# Sheme.net
KiCad netlist of a schematic drawn in Altium Designer
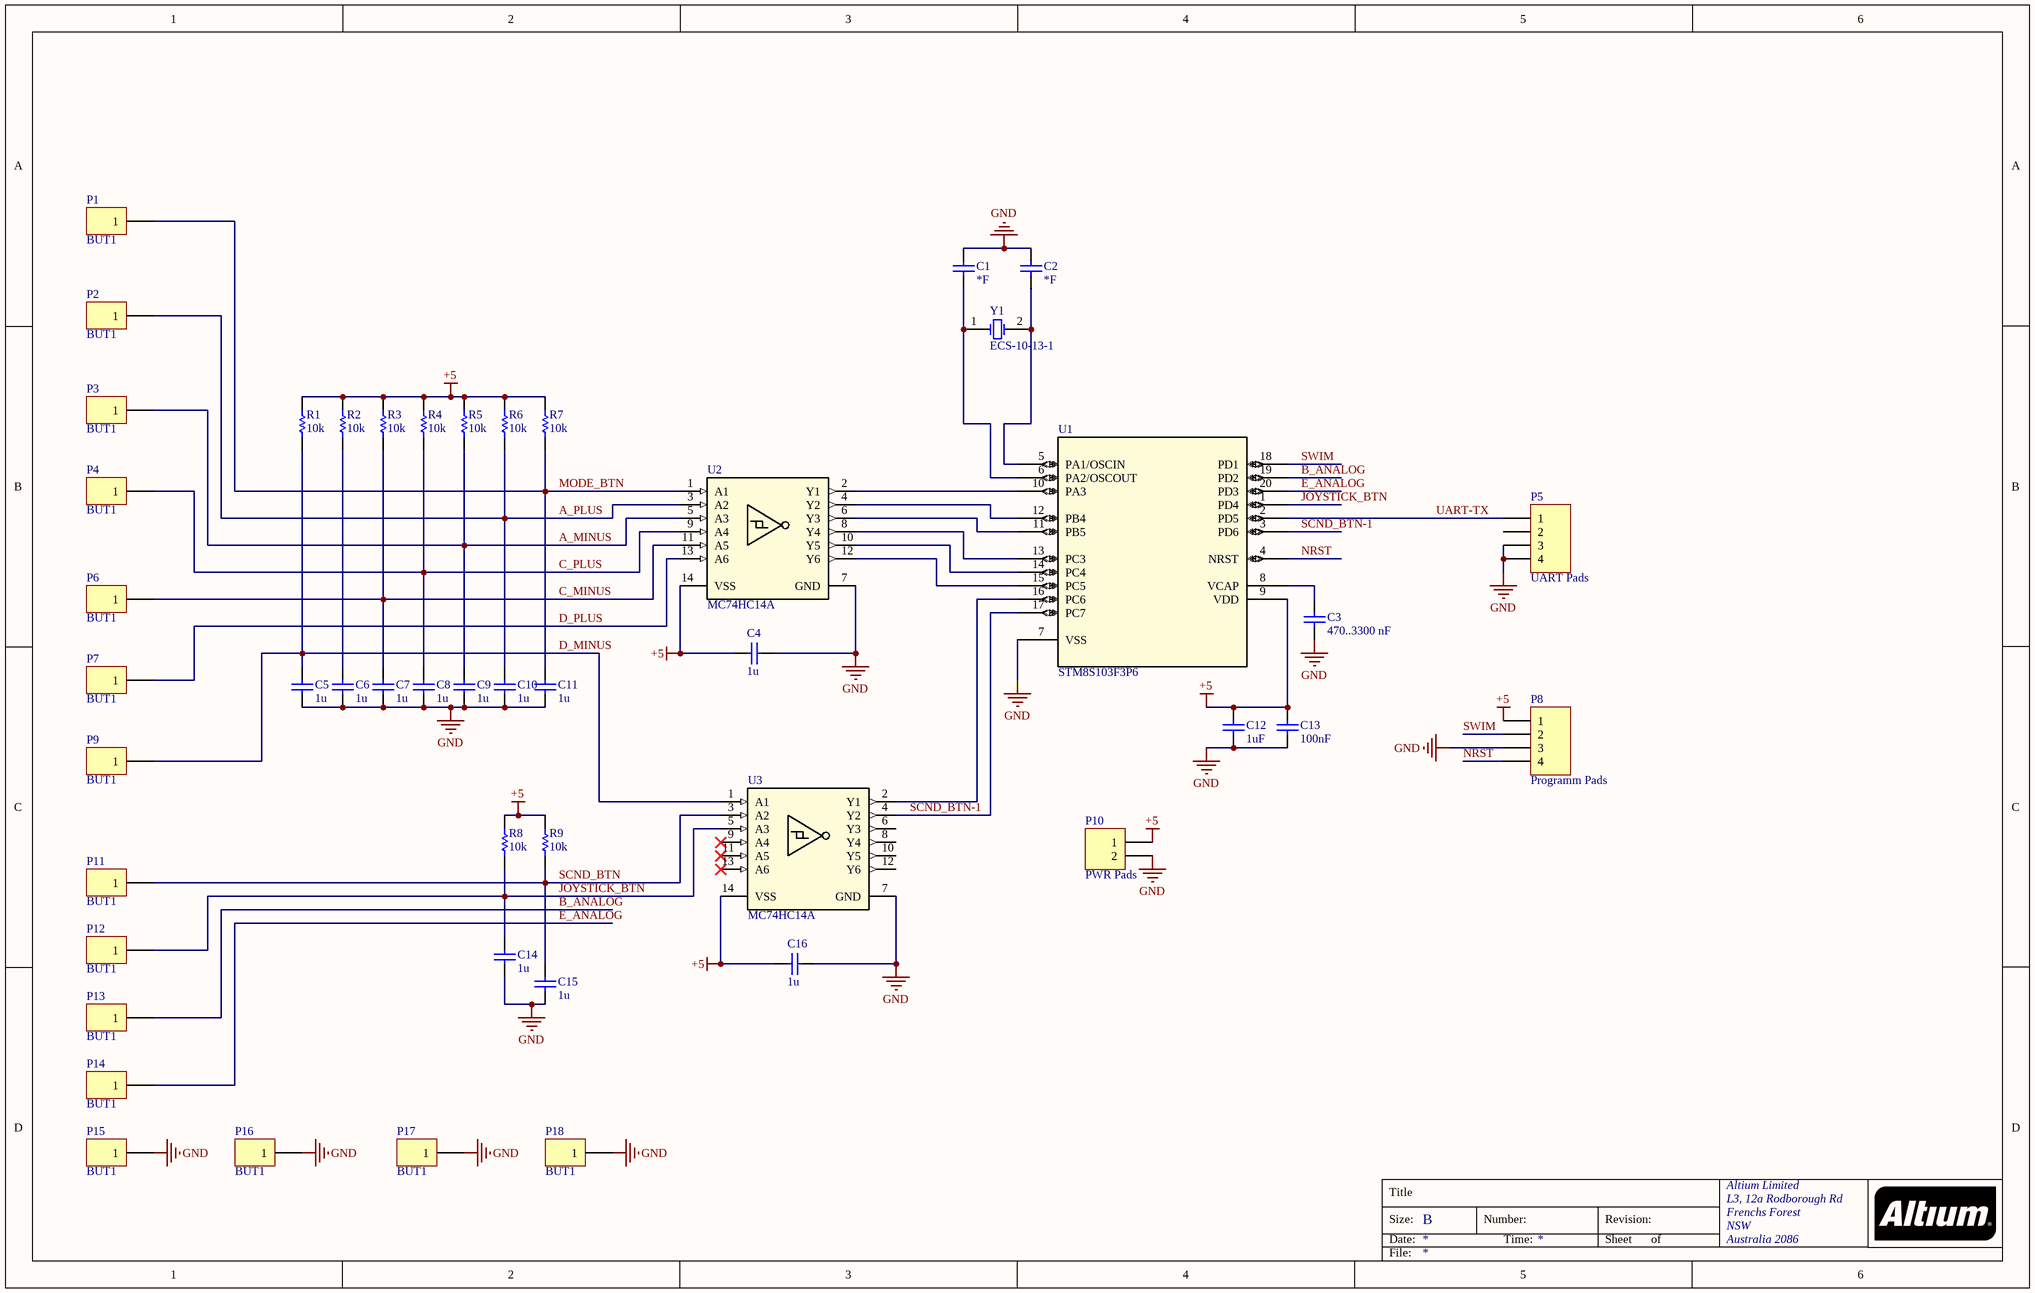
[diagram p0: Sheme.SchDoc]

(export (version "E")
  (design (tool "Eeschema 10.0.6"))
  (components
    (comp (ref "C1")
      (value "*F")
      (footprint "C0805")
      (description "Capacitor ceramic SMD")
      (fields (field (name "MANUFACTURER") "Murata") (field (name "Comment") "Cap"))
      (libsource (lib "DriverBoardForCNC") (part "Cap"))
    )
    (comp (ref "C2")
      (value "*F")
      (footprint "C0805")
      (description "Capacitor ceramic SMD")
      (fields (field (name "MANUFACTURER") "Murata") (field (name "Comment") "Cap"))
      (libsource (lib "DriverBoardForCNC") (part "Cap"))
    )
    (comp (ref "C3")
      (value "470..3300 nF")
      (footprint "C0805")
      (description "Capacitor ceramic SMD")
      (fields (field (name "MANUFACTURER") "Murata") (field (name "Comment") "Cap"))
      (libsource (lib "DriverBoardForCNC") (part "Cap"))
    )
    (comp (ref "C4")
      (value "1u")
      (footprint "C0805")
      (description "Capacitor ceramic SMD")
      (fields (field (name "MANUFACTURER") "Murata") (field (name "Comment") "Cap"))
      (libsource (lib "DriverBoardForCNC") (part "Cap"))
    )
    (comp (ref "C5")
      (value "1u")
      (footprint "C0805")
      (description "Capacitor ceramic SMD")
      (fields (field (name "MANUFACTURER") "Murata") (field (name "Comment") "Cap"))
      (libsource (lib "DriverBoardForCNC") (part "Cap"))
    )
    (comp (ref "C6")
      (value "1u")
      (footprint "C0805")
      (description "Capacitor ceramic SMD")
      (fields (field (name "MANUFACTURER") "Murata") (field (name "Comment") "Cap"))
      (libsource (lib "DriverBoardForCNC") (part "Cap"))
    )
    (comp (ref "C7")
      (value "1u")
      (footprint "C0805")
      (description "Capacitor ceramic SMD")
      (fields (field (name "MANUFACTURER") "Murata") (field (name "Comment") "Cap"))
      (libsource (lib "DriverBoardForCNC") (part "Cap"))
    )
    (comp (ref "C8")
      (value "1u")
      (footprint "C0805")
      (description "Capacitor ceramic SMD")
      (fields (field (name "MANUFACTURER") "Murata") (field (name "Comment") "Cap"))
      (libsource (lib "DriverBoardForCNC") (part "Cap"))
    )
    (comp (ref "C9")
      (value "1u")
      (footprint "C0805")
      (description "Capacitor ceramic SMD")
      (fields (field (name "MANUFACTURER") "Murata") (field (name "Comment") "Cap"))
      (libsource (lib "DriverBoardForCNC") (part "Cap"))
    )
    (comp (ref "C10")
      (value "1u")
      (footprint "C0805")
      (description "Capacitor ceramic SMD")
      (fields (field (name "MANUFACTURER") "Murata") (field (name "Comment") "Cap"))
      (libsource (lib "DriverBoardForCNC") (part "Cap"))
    )
    (comp (ref "C11")
      (value "1u")
      (footprint "C0805")
      (description "Capacitor ceramic SMD")
      (fields (field (name "MANUFACTURER") "Murata") (field (name "Comment") "Cap"))
      (libsource (lib "DriverBoardForCNC") (part "Cap"))
    )
    (comp (ref "C12")
      (value "1uF")
      (footprint "C0805")
      (description "Capacitor ceramic SMD")
      (fields (field (name "MANUFACTURER") "Murata") (field (name "Comment") "Cap"))
      (libsource (lib "DriverBoardForCNC") (part "Cap"))
    )
    (comp (ref "C13")
      (value "100nF")
      (footprint "C0805")
      (description "Capacitor ceramic SMD")
      (fields (field (name "MANUFACTURER") "Murata") (field (name "Comment") "Cap"))
      (libsource (lib "DriverBoardForCNC") (part "Cap"))
    )
    (comp (ref "C14")
      (value "1u")
      (footprint "C0805")
      (description "Capacitor ceramic SMD")
      (fields (field (name "MANUFACTURER") "Murata") (field (name "Comment") "Cap"))
      (libsource (lib "DriverBoardForCNC") (part "Cap"))
    )
    (comp (ref "C15")
      (value "1u")
      (footprint "C0805")
      (description "Capacitor ceramic SMD")
      (fields (field (name "MANUFACTURER") "Murata") (field (name "Comment") "Cap"))
      (libsource (lib "DriverBoardForCNC") (part "Cap"))
    )
    (comp (ref "C16")
      (value "1u")
      (footprint "C0805")
      (description "Capacitor ceramic SMD")
      (fields (field (name "MANUFACTURER") "Murata") (field (name "Comment") "Cap"))
      (libsource (lib "DriverBoardForCNC") (part "Cap"))
    )
    (comp (ref "P1") (value "BUT1") (footprint "1pin-smd") (libsource (lib "Schlib1") (part "Header 1")))
    (comp (ref "P2") (value "BUT1") (footprint "1pin-smd") (libsource (lib "Schlib1") (part "Header 1")))
    (comp (ref "P3") (value "BUT1") (footprint "1pin-smd") (libsource (lib "Schlib1") (part "Header 1")))
    (comp (ref "P4") (value "BUT1") (footprint "1pin-smd") (libsource (lib "Schlib1") (part "Header 1")))
    (comp (ref "P5")
      (value "UART Pads")
      (footprint "HDR1X4")
      (description "Header, 4-Pin")
      (fields (field (name "MANUFACTURER") "Re-released for DXP Platform."))
      (libsource (lib "DriverBoardForCNC") (part "Header 4"))
    )
    (comp (ref "P6") (value "BUT1") (footprint "1pin-smd") (libsource (lib "Schlib1") (part "Header 1")))
    (comp (ref "P7") (value "BUT1") (footprint "1pin-smd") (libsource (lib "Schlib1") (part "Header 1")))
    (comp (ref "P8")
      (value "Programm Pads")
      (footprint "HDR1X4")
      (description "Header, 4-Pin")
      (fields (field (name "MANUFACTURER") "Re-released for DXP Platform."))
      (libsource (lib "DriverBoardForCNC") (part "Header 4"))
    )
    (comp (ref "P9") (value "BUT1") (footprint "1pin-smd") (libsource (lib "Schlib1") (part "Header 1")))
    (comp (ref "P10")
      (value "PWR Pads")
      (footprint "2pin-smd")
      (description "Header, 2-Pin")
      (libsource (lib "DriverBoardForCNC") (part "Header 2"))
    )
    (comp (ref "P11") (value "BUT1") (footprint "1pin-smd") (libsource (lib "Schlib1") (part "Header 1")))
    (comp (ref "P12") (value "BUT1") (footprint "1pin-smd") (libsource (lib "Schlib1") (part "Header 1")))
    (comp (ref "P13") (value "BUT1") (footprint "1pin-smd") (libsource (lib "Schlib1") (part "Header 1")))
    (comp (ref "P14") (value "BUT1") (footprint "1pin-smd") (libsource (lib "Schlib1") (part "Header 1")))
    (comp (ref "P15") (value "BUT1") (footprint "1pin-smd") (libsource (lib "Schlib1") (part "Header 1")))
    (comp (ref "P16") (value "BUT1") (footprint "1pin-smd") (libsource (lib "Schlib1") (part "Header 1")))
    (comp (ref "P17") (value "BUT1") (footprint "1pin-smd") (libsource (lib "Schlib1") (part "Header 1")))
    (comp (ref "P18") (value "BUT1") (footprint "1pin-smd") (libsource (lib "Schlib1") (part "Header 1")))
    (comp (ref "R1")
      (value "10k")
      (footprint "RES-0805")
      (description "Rectangular Thick Film Chip Resistor")
      (fields
        (field (name "MANUFACTURER_PART_NUMBER") "17-Dec-2003")
        (field (name "MANUFACTURER") "Altium Limited")
      )
      (libsource (lib "DriverBoardForCNC") (part "Res"))
    )
    (comp (ref "R2")
      (value "10k")
      (footprint "RES-0805")
      (description "Rectangular Thick Film Chip Resistor")
      (fields
        (field (name "MANUFACTURER_PART_NUMBER") "17-Dec-2003")
        (field (name "MANUFACTURER") "Altium Limited")
      )
      (libsource (lib "DriverBoardForCNC") (part "Res"))
    )
    (comp (ref "R3")
      (value "10k")
      (footprint "RES-0805")
      (description "Rectangular Thick Film Chip Resistor")
      (fields
        (field (name "MANUFACTURER_PART_NUMBER") "17-Dec-2003")
        (field (name "MANUFACTURER") "Altium Limited")
      )
      (libsource (lib "DriverBoardForCNC") (part "Res"))
    )
    (comp (ref "R4")
      (value "10k")
      (footprint "RES-0805")
      (description "Rectangular Thick Film Chip Resistor")
      (fields
        (field (name "MANUFACTURER_PART_NUMBER") "17-Dec-2003")
        (field (name "MANUFACTURER") "Altium Limited")
      )
      (libsource (lib "DriverBoardForCNC") (part "Res"))
    )
    (comp (ref "R5")
      (value "10k")
      (footprint "RES-0805")
      (description "Rectangular Thick Film Chip Resistor")
      (fields
        (field (name "MANUFACTURER_PART_NUMBER") "17-Dec-2003")
        (field (name "MANUFACTURER") "Altium Limited")
      )
      (libsource (lib "DriverBoardForCNC") (part "Res"))
    )
    (comp (ref "R6")
      (value "10k")
      (footprint "RES-0805")
      (description "Rectangular Thick Film Chip Resistor")
      (fields
        (field (name "MANUFACTURER_PART_NUMBER") "17-Dec-2003")
        (field (name "MANUFACTURER") "Altium Limited")
      )
      (libsource (lib "DriverBoardForCNC") (part "Res"))
    )
    (comp (ref "R7")
      (value "10k")
      (footprint "RES-0805")
      (description "Rectangular Thick Film Chip Resistor")
      (fields
        (field (name "MANUFACTURER_PART_NUMBER") "17-Dec-2003")
        (field (name "MANUFACTURER") "Altium Limited")
      )
      (libsource (lib "DriverBoardForCNC") (part "Res"))
    )
    (comp (ref "R8")
      (value "10k")
      (footprint "RES-0805")
      (description "Rectangular Thick Film Chip Resistor")
      (fields
        (field (name "MANUFACTURER_PART_NUMBER") "17-Dec-2003")
        (field (name "MANUFACTURER") "Altium Limited")
      )
      (libsource (lib "DriverBoardForCNC") (part "Res"))
    )
    (comp (ref "R9")
      (value "10k")
      (footprint "RES-0805")
      (description "Rectangular Thick Film Chip Resistor")
      (fields
        (field (name "MANUFACTURER_PART_NUMBER") "17-Dec-2003")
        (field (name "MANUFACTURER") "Altium Limited")
      )
      (libsource (lib "DriverBoardForCNC") (part "Res"))
    )
    (comp (ref "U1")
      (value "STM8S103F3P6")
      (footprint "SSOP20")
      (description "No Description Available")
      (fields (field (name "COPYRIGHT") "Copyright (C) 2022 Ultra Librarian. All rights reserved."))
      (libsource (lib "STM8S103F3P6") (part "STM8S103F3P6"))
    )
    (comp (ref "U2")
      (value "MC74HC14A")
      (footprint "SOIC-14_N")
      (description "Hex Schmitt-Trigger\r\nInverter")
      (fields (field (name "COPYRIGHT") "Copyright (C) 2022 Ultra Librarian. All rights reserved."))
      (libsource (lib "ICs digital") (part "MC74HC14A"))
    )
    (comp (ref "U3")
      (value "MC74HC14A")
      (footprint "SOIC-14_N")
      (description "Hex Schmitt-Trigger\r\nInverter")
      (fields (field (name "COPYRIGHT") "Copyright (C) 2022 Ultra Librarian. All rights reserved."))
      (libsource (lib "ICs digital") (part "MC74HC14A"))
    )
    (comp (ref "Y1")
      (value "ECS-10-13-1")
      (footprint "HC-49U")
      (description "Crystal Oscillator")
      (fields (field (name "PUBLISHER") "Altium Limited"))
      (libsource (lib "ECS Crystal Oscillator") (part "ECS-10-13-1"))
    )
  )
  (nets
    (net (code "1") (name "+5") (class "Default")
      (node (ref "C12") (pin "2") (pinfunction "2_2") (pintype "passive"))
      (node (ref "C13") (pin "2") (pinfunction "2_2") (pintype "passive"))
      (node (ref "C16") (pin "2") (pinfunction "2_2") (pintype "passive"))
      (node (ref "C4") (pin "2") (pinfunction "2_2") (pintype "passive"))
      (node (ref "P10") (pin "1") (pinfunction "1_1") (pintype "passive"))
      (node (ref "P8") (pin "1") (pinfunction "1_1") (pintype "passive"))
      (node (ref "R1") (pin "2") (pinfunction "2_2") (pintype "passive"))
      (node (ref "R2") (pin "2") (pinfunction "2_2") (pintype "passive"))
      (node (ref "R3") (pin "2") (pinfunction "2_2") (pintype "passive"))
      (node (ref "R4") (pin "2") (pinfunction "2_2") (pintype "passive"))
      (node (ref "R5") (pin "2") (pinfunction "2_2") (pintype "passive"))
      (node (ref "R6") (pin "2") (pinfunction "2_2") (pintype "passive"))
      (node (ref "R7") (pin "2") (pinfunction "2_2") (pintype "passive"))
      (node (ref "R8") (pin "2") (pinfunction "2_2") (pintype "passive"))
      (node (ref "R9") (pin "2") (pinfunction "2_2") (pintype "passive"))
      (node (ref "U1") (pin "9") (pinfunction "VDD_9") (pintype "power_in"))
      (node (ref "U2") (pin "14") (pinfunction "VSS_14") (pintype "power_in"))
      (node (ref "U3") (pin "14") (pinfunction "VSS_14") (pintype "power_in"))
    )
    (net (code "2") (name "/A_MINUS") (class "Default")
      (node (ref "C9") (pin "2") (pinfunction "2_2") (pintype "passive"))
      (node (ref "P3") (pin "1") (pinfunction "1_1") (pintype "passive"))
      (node (ref "R5") (pin "1") (pinfunction "1_1") (pintype "passive"))
      (node (ref "U2") (pin "5") (pinfunction "A3_5") (pintype "input"))
    )
    (net (code "3") (name "/A_PLUS") (class "Default")
      (node (ref "C10") (pin "2") (pinfunction "2_2") (pintype "passive"))
      (node (ref "P2") (pin "1") (pinfunction "1_1") (pintype "passive"))
      (node (ref "R6") (pin "1") (pinfunction "1_1") (pintype "passive"))
      (node (ref "U2") (pin "3") (pinfunction "A2_3") (pintype "input"))
    )
    (net (code "4") (name "/B_ANALOG") (class "Default")
      (node (ref "P13") (pin "1") (pinfunction "1_1") (pintype "passive"))
      (node (ref "U1") (pin "19") (pinfunction "PD2_19") (pintype "bidirectional"))
    )
    (net (code "5") (name "/C_MINUS") (class "Default")
      (node (ref "C7") (pin "2") (pinfunction "2_2") (pintype "passive"))
      (node (ref "P6") (pin "1") (pinfunction "1_1") (pintype "passive"))
      (node (ref "R3") (pin "1") (pinfunction "1_1") (pintype "passive"))
      (node (ref "U2") (pin "11") (pinfunction "A5_11") (pintype "input"))
    )
    (net (code "6") (name "/C_PLUS") (class "Default")
      (node (ref "C8") (pin "2") (pinfunction "2_2") (pintype "passive"))
      (node (ref "P4") (pin "1") (pinfunction "1_1") (pintype "passive"))
      (node (ref "R4") (pin "1") (pinfunction "1_1") (pintype "passive"))
      (node (ref "U2") (pin "9") (pinfunction "A4_9") (pintype "input"))
    )
    (net (code "7") (name "/D_MINUS") (class "Default")
      (node (ref "C5") (pin "2") (pinfunction "2_2") (pintype "passive"))
      (node (ref "P9") (pin "1") (pinfunction "1_1") (pintype "passive"))
      (node (ref "R1") (pin "1") (pinfunction "1_1") (pintype "passive"))
      (node (ref "U3") (pin "1") (pinfunction "A1_1") (pintype "input"))
    )
    (net (code "8") (name "/D_PLUS") (class "Default")
      (node (ref "P7") (pin "1") (pinfunction "1_1") (pintype "passive"))
      (node (ref "U2") (pin "13") (pinfunction "A6_13") (pintype "input"))
    )
    (net (code "9") (name "/E_ANALOG") (class "Default")
      (node (ref "P14") (pin "1") (pinfunction "1_1") (pintype "passive"))
      (node (ref "U1") (pin "20") (pinfunction "PD3_20") (pintype "bidirectional"))
    )
    (net (code "10") (name "/JOYSTICK_BTN") (class "Default")
      (node (ref "C14") (pin "2") (pinfunction "2_2") (pintype "passive"))
      (node (ref "P12") (pin "1") (pinfunction "1_1") (pintype "passive"))
      (node (ref "R8") (pin "1") (pinfunction "1_1") (pintype "passive"))
      (node (ref "U1") (pin "1") (pinfunction "PD4_1") (pintype "bidirectional"))
      (node (ref "U3") (pin "5") (pinfunction "A3_5") (pintype "input"))
    )
    (net (code "11") (name "/MODE_BTN") (class "Default")
      (node (ref "C11") (pin "2") (pinfunction "2_2") (pintype "passive"))
      (node (ref "P1") (pin "1") (pinfunction "1_1") (pintype "passive"))
      (node (ref "R7") (pin "1") (pinfunction "1_1") (pintype "passive"))
      (node (ref "U2") (pin "1") (pinfunction "A1_1") (pintype "input"))
    )
    (net (code "12") (name "/NRST") (class "Default")
      (node (ref "P8") (pin "4") (pinfunction "4_4") (pintype "passive"))
      (node (ref "U1") (pin "4") (pinfunction "NRST_4") (pintype "bidirectional"))
    )
    (net (code "13") (name "/SCND_BTN") (class "Default")
      (node (ref "C15") (pin "2") (pinfunction "2_2") (pintype "passive"))
      (node (ref "P11") (pin "1") (pinfunction "1_1") (pintype "passive"))
      (node (ref "R9") (pin "1") (pinfunction "1_1") (pintype "passive"))
      (node (ref "U3") (pin "3") (pinfunction "A2_3") (pintype "input"))
    )
    (net (code "14") (name "/SCND_BTN-1") (class "Default")
      (node (ref "U1") (pin "17") (pinfunction "PC7_17") (pintype "bidirectional"))
      (node (ref "U1") (pin "3") (pinfunction "PD6_3") (pintype "bidirectional"))
      (node (ref "U3") (pin "4") (pinfunction "Y2_4") (pintype "output"))
    )
    (net (code "15") (name "/SWIM") (class "Default")
      (node (ref "P8") (pin "2") (pinfunction "2_2") (pintype "passive"))
      (node (ref "U1") (pin "18") (pinfunction "PD1_18") (pintype "bidirectional"))
    )
    (net (code "16") (name "/UART-TX") (class "Default")
      (node (ref "P5") (pin "1") (pinfunction "1_1") (pintype "passive"))
      (node (ref "U1") (pin "2") (pinfunction "PD5_2") (pintype "bidirectional"))
    )
    (net (code "17") (name "GND") (class "Default")
      (node (ref "C1") (pin "2") (pinfunction "2_2") (pintype "passive"))
      (node (ref "C10") (pin "1") (pinfunction "1_1") (pintype "passive"))
      (node (ref "C11") (pin "1") (pinfunction "1_1") (pintype "passive"))
      (node (ref "C12") (pin "1") (pinfunction "1_1") (pintype "passive"))
      (node (ref "C13") (pin "1") (pinfunction "1_1") (pintype "passive"))
      (node (ref "C14") (pin "1") (pinfunction "1_1") (pintype "passive"))
      (node (ref "C15") (pin "1") (pinfunction "1_1") (pintype "passive"))
      (node (ref "C16") (pin "1") (pinfunction "1_1") (pintype "passive"))
      (node (ref "C2") (pin "2") (pinfunction "2_2") (pintype "passive"))
      (node (ref "C3") (pin "1") (pinfunction "1_1") (pintype "passive"))
      (node (ref "C4") (pin "1") (pinfunction "1_1") (pintype "passive"))
      (node (ref "C5") (pin "1") (pinfunction "1_1") (pintype "passive"))
      (node (ref "C6") (pin "1") (pinfunction "1_1") (pintype "passive"))
      (node (ref "C7") (pin "1") (pinfunction "1_1") (pintype "passive"))
      (node (ref "C8") (pin "1") (pinfunction "1_1") (pintype "passive"))
      (node (ref "C9") (pin "1") (pinfunction "1_1") (pintype "passive"))
      (node (ref "P10") (pin "2") (pinfunction "2_2") (pintype "passive"))
      (node (ref "P15") (pin "1") (pinfunction "1_1") (pintype "passive"))
      (node (ref "P16") (pin "1") (pinfunction "1_1") (pintype "passive"))
      (node (ref "P17") (pin "1") (pinfunction "1_1") (pintype "passive"))
      (node (ref "P18") (pin "1") (pinfunction "1_1") (pintype "passive"))
      (node (ref "P5") (pin "3") (pinfunction "3_3") (pintype "passive"))
      (node (ref "P5") (pin "4") (pinfunction "4_4") (pintype "passive"))
      (node (ref "P8") (pin "3") (pinfunction "3_3") (pintype "passive"))
      (node (ref "U1") (pin "7") (pinfunction "VSS_7") (pintype "power_in"))
      (node (ref "U2") (pin "7") (pinfunction "GND_7") (pintype "power_in"))
      (node (ref "U3") (pin "7") (pinfunction "GND_7") (pintype "power_in"))
    )
    (net (code "18") (name "Net-(C6-Pad2)") (class "Default")
      (node (ref "C6") (pin "2") (pinfunction "2_2") (pintype "passive"))
      (node (ref "R2") (pin "1") (pinfunction "1_1") (pintype "passive"))
    )
    (net (code "19") (name "Net-(U1-PA1{slash}OSCIN)") (class "Default")
      (node (ref "C2") (pin "1") (pinfunction "1_1") (pintype "passive"))
      (node (ref "U1") (pin "5") (pinfunction "PA1/OSCIN_5") (pintype "bidirectional"))
      (node (ref "Y1") (pin "2") (pinfunction "OSC2_2") (pintype "passive"))
    )
    (net (code "20") (name "Net-(U1-PA2{slash}OSCOUT)") (class "Default")
      (node (ref "C1") (pin "1") (pinfunction "1_1") (pintype "passive"))
      (node (ref "U1") (pin "6") (pinfunction "PA2/OSCOUT_6") (pintype "bidirectional"))
      (node (ref "Y1") (pin "1") (pinfunction "OSC1_1") (pintype "passive"))
    )
    (net (code "21") (name "Net-(U1-PA3)") (class "Default")
      (node (ref "U1") (pin "10") (pinfunction "PA3_10") (pintype "bidirectional"))
      (node (ref "U2") (pin "2") (pinfunction "Y1_2") (pintype "output"))
    )
    (net (code "22") (name "Net-(U1-PB4)") (class "Default")
      (node (ref "U1") (pin "12") (pinfunction "PB4_12") (pintype "bidirectional"))
      (node (ref "U2") (pin "4") (pinfunction "Y2_4") (pintype "output"))
    )
    (net (code "23") (name "Net-(U1-PB5)") (class "Default")
      (node (ref "U1") (pin "11") (pinfunction "PB5_11") (pintype "bidirectional"))
      (node (ref "U2") (pin "6") (pinfunction "Y3_6") (pintype "output"))
    )
    (net (code "24") (name "Net-(U1-PC3)") (class "Default")
      (node (ref "U1") (pin "13") (pinfunction "PC3_13") (pintype "bidirectional"))
      (node (ref "U2") (pin "8") (pinfunction "Y4_8") (pintype "output"))
    )
    (net (code "25") (name "Net-(U1-PC4)") (class "Default")
      (node (ref "U1") (pin "14") (pinfunction "PC4_14") (pintype "bidirectional"))
      (node (ref "U2") (pin "10") (pinfunction "Y5_10") (pintype "output"))
    )
    (net (code "26") (name "Net-(U1-PC5)") (class "Default")
      (node (ref "U1") (pin "15") (pinfunction "PC5_15") (pintype "bidirectional"))
      (node (ref "U2") (pin "12") (pinfunction "Y6_12") (pintype "output"))
    )
    (net (code "27") (name "Net-(U1-PC6)") (class "Default")
      (node (ref "U1") (pin "16") (pinfunction "PC6_16") (pintype "bidirectional"))
      (node (ref "U3") (pin "2") (pinfunction "Y1_2") (pintype "output"))
    )
    (net (code "28") (name "Net-(U1-VCAP)") (class "Default")
      (node (ref "C3") (pin "2") (pinfunction "2_2") (pintype "passive"))
      (node (ref "U1") (pin "8") (pinfunction "VCAP_8") (pintype "power_in"))
    )
    (net (code "29") (name "unconnected-(P5-Pad2)") (class "Default")
      (node (ref "P5") (pin "2") (pinfunction "2_2") (pintype "passive"))
    )
    (net (code "30") (name "unconnected-(U3-A4-Pad9)") (class "Default")
      (node (ref "U3") (pin "9") (pinfunction "A4_9") (pintype "input+no_connect"))
    )
    (net (code "31") (name "unconnected-(U3-A5-Pad11)") (class "Default")
      (node (ref "U3") (pin "11") (pinfunction "A5_11") (pintype "input+no_connect"))
    )
    (net (code "32") (name "unconnected-(U3-A6-Pad13)") (class "Default")
      (node (ref "U3") (pin "13") (pinfunction "A6_13") (pintype "input+no_connect"))
    )
    (net (code "33") (name "unconnected-(U3-Y3-Pad6)") (class "Default")
      (node (ref "U3") (pin "6") (pinfunction "Y3_6") (pintype "output"))
    )
    (net (code "34") (name "unconnected-(U3-Y4-Pad8)") (class "Default")
      (node (ref "U3") (pin "8") (pinfunction "Y4_8") (pintype "output"))
    )
    (net (code "35") (name "unconnected-(U3-Y5-Pad10)") (class "Default")
      (node (ref "U3") (pin "10") (pinfunction "Y5_10") (pintype "output"))
    )
    (net (code "36") (name "unconnected-(U3-Y6-Pad12)") (class "Default")
      (node (ref "U3") (pin "12") (pinfunction "Y6_12") (pintype "output"))
    )
  )
)
